# UBTB_MIX.net
KiCad netlist of a schematic drawn in EAGLE
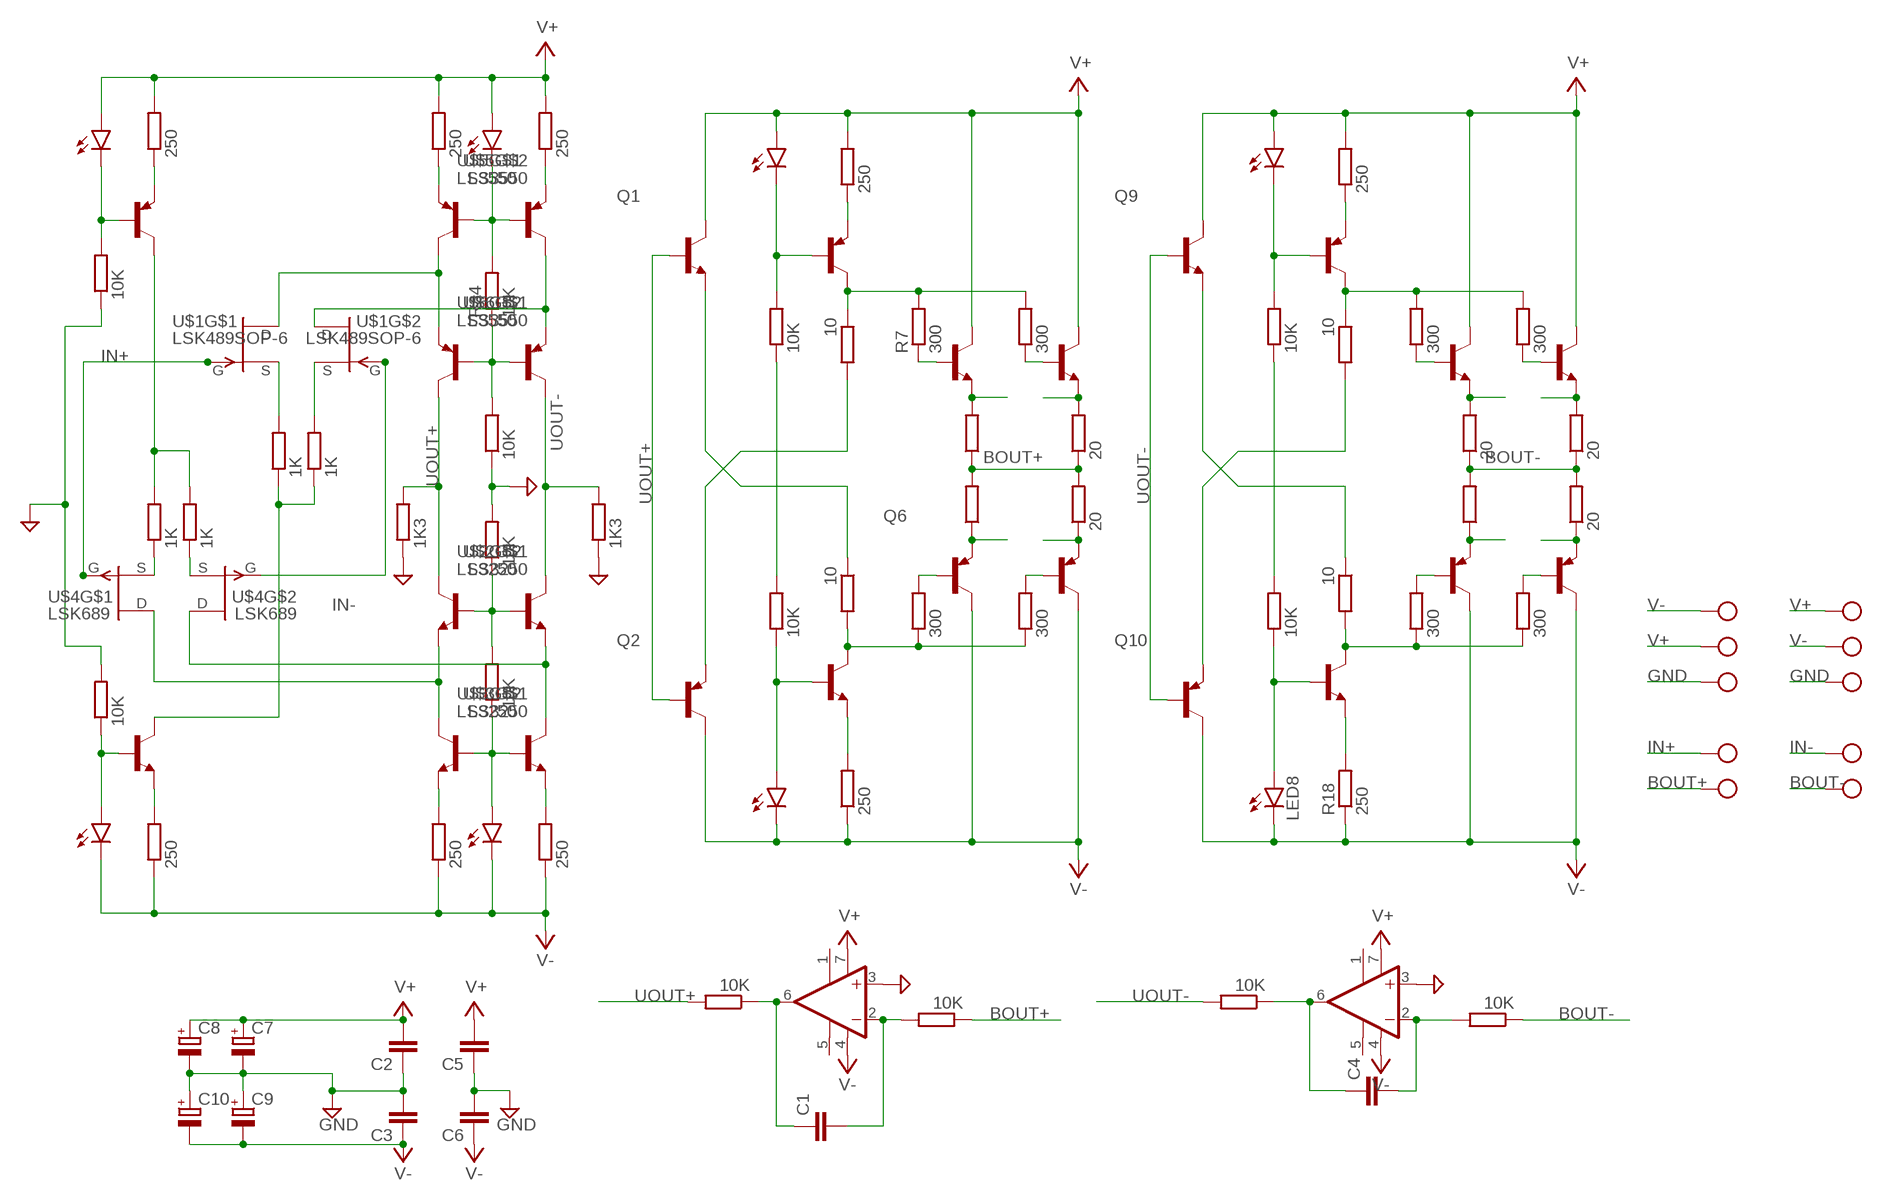
[diagram p0: schematic, sheet 1]

(export (version "E")
  (design (tool "Eeschema 10.0.6"))
  (components
    (comp (ref "C1")
      (value "C-EUC1206")
      (footprint "eagle-import:C1206")
      (libsource (lib "eagle-import") (part "C-EUC1206"))
    )
    (comp (ref "C2")
      (value "C-EUC0805")
      (footprint "eagle-import:C0805")
      (libsource (lib "eagle-import") (part "C-EUC0805"))
    )
    (comp (ref "C3")
      (value "C-EUC0805")
      (footprint "eagle-import:C0805")
      (libsource (lib "eagle-import") (part "C-EUC0805"))
    )
    (comp (ref "C4")
      (value "C-EUC1206")
      (footprint "eagle-import:C1206")
      (libsource (lib "eagle-import") (part "C-EUC1206"))
    )
    (comp (ref "C5")
      (value "C-EUC0805")
      (footprint "eagle-import:C0805")
      (libsource (lib "eagle-import") (part "C-EUC0805"))
    )
    (comp (ref "C6")
      (value "C-EUC0805")
      (footprint "eagle-import:C0805")
      (libsource (lib "eagle-import") (part "C-EUC0805"))
    )
    (comp (ref "C7")
      (value "CPOL-EUF")
      (footprint "eagle-import:PANASONIC_F")
      (libsource (lib "eagle-import") (part "CPOL-EUF"))
    )
    (comp (ref "C8")
      (value "CPOL-EUF")
      (footprint "eagle-import:PANASONIC_F")
      (libsource (lib "eagle-import") (part "CPOL-EUF"))
    )
    (comp (ref "C9")
      (value "CPOL-EUF")
      (footprint "eagle-import:PANASONIC_F")
      (libsource (lib "eagle-import") (part "CPOL-EUF"))
    )
    (comp (ref "C10")
      (value "CPOL-EUF")
      (footprint "eagle-import:PANASONIC_F")
      (libsource (lib "eagle-import") (part "CPOL-EUF"))
    )
    (comp (ref "IC1")
      (value "OPA627U")
      (footprint "eagle-import:SO08")
      (fields (field (name "MF") "TEXAS INSTRUMENTS") (field (name "MPN") "OPA627AU"))
      (libsource (lib "eagle-import") (part "OPA627U"))
    )
    (comp (ref "IC2")
      (value "OPA627U")
      (footprint "eagle-import:SO08")
      (fields (field (name "MF") "TEXAS INSTRUMENTS") (field (name "MPN") "OPA627AU"))
      (libsource (lib "eagle-import") (part "OPA627U"))
    )
    (comp (ref "LED1")
      (value "LEDVWV1206")
      (footprint "eagle-import:LED_SML1206")
      (libsource (lib "eagle-import") (part "LEDVWV1206"))
    )
    (comp (ref "LED2")
      (value "LEDVWV1206")
      (footprint "eagle-import:LED_SML1206")
      (libsource (lib "eagle-import") (part "LEDVWV1206"))
    )
    (comp (ref "LED3")
      (value "LEDVWV1206")
      (footprint "eagle-import:LED_SML1206")
      (libsource (lib "eagle-import") (part "LEDVWV1206"))
    )
    (comp (ref "LED4")
      (value "LEDVWV1206")
      (footprint "eagle-import:LED_SML1206")
      (fields (field (name "SPICEPREFIX") "D"))
      (libsource (lib "eagle-import") (part "LEDVWV1206"))
    )
    (comp (ref "LED5")
      (value "LEDVWV1206")
      (footprint "eagle-import:LED_SML1206")
      (libsource (lib "eagle-import") (part "LEDVWV1206"))
    )
    (comp (ref "LED6")
      (value "LEDVWV1206")
      (footprint "eagle-import:LED_SML1206")
      (libsource (lib "eagle-import") (part "LEDVWV1206"))
    )
    (comp (ref "LED7")
      (value "LEDVWV1206")
      (footprint "eagle-import:LED_SML1206")
      (libsource (lib "eagle-import") (part "LEDVWV1206"))
    )
    (comp (ref "LED8")
      (value "LEDVWV1206")
      (footprint "eagle-import:LED_SML1206")
      (libsource (lib "eagle-import") (part "LEDVWV1206"))
    )
    (comp (ref "Q1")
      (value "TRANSISTOR_BC846-NPN-SOT23-BEC")
      (footprint "eagle-import:TRANSISTOR_SOT23-BEC")
      (libsource (lib "eagle-import") (part "TRANSISTOR_-NPN-SOT23-BECBC846"))
    )
    (comp (ref "Q2")
      (value "TRANSISTOR_BC856B-PNP-SOT23-BEC")
      (footprint "eagle-import:TRANSISTOR_SOT23-BEC")
      (libsource (lib "eagle-import") (part "TRANSISTOR_-PNP-SOT23-BECBC856B"))
    )
    (comp (ref "Q3")
      (value "TRANSISTOR_BC846-NPN-SOT23-BEC")
      (footprint "eagle-import:TRANSISTOR_SOT23-BEC")
      (libsource (lib "eagle-import") (part "TRANSISTOR_-NPN-SOT23-BECBC846"))
    )
    (comp (ref "Q4")
      (value "TRANSISTOR_BC856B-PNP-SOT23-BEC")
      (footprint "eagle-import:TRANSISTOR_SOT23-BEC")
      (libsource (lib "eagle-import") (part "TRANSISTOR_-PNP-SOT23-BECBC856B"))
    )
    (comp (ref "Q5")
      (value "TRANSISTOR_BC846-NPN-SOT23-BEC")
      (footprint "eagle-import:TRANSISTOR_SOT23-BEC")
      (libsource (lib "eagle-import") (part "TRANSISTOR_-NPN-SOT23-BECBC846"))
    )
    (comp (ref "Q6")
      (value "TRANSISTOR_BC856B-PNP-SOT23-BEC")
      (footprint "eagle-import:TRANSISTOR_SOT23-BEC")
      (libsource (lib "eagle-import") (part "TRANSISTOR_-PNP-SOT23-BECBC856B"))
    )
    (comp (ref "Q7")
      (value "TRANSISTOR_BC856B-PNP-SOT23-BEC")
      (footprint "eagle-import:TRANSISTOR_SOT23-BEC")
      (libsource (lib "eagle-import") (part "TRANSISTOR_-PNP-SOT23-BECBC856B"))
    )
    (comp (ref "Q8")
      (value "TRANSISTOR_BC846-NPN-SOT23-BEC")
      (footprint "eagle-import:TRANSISTOR_SOT23-BEC")
      (libsource (lib "eagle-import") (part "TRANSISTOR_-NPN-SOT23-BECBC846"))
    )
    (comp (ref "Q9")
      (value "TRANSISTOR_BC846-NPN-SOT23-BEC")
      (footprint "eagle-import:TRANSISTOR_SOT23-BEC")
      (libsource (lib "eagle-import") (part "TRANSISTOR_-NPN-SOT23-BECBC846"))
    )
    (comp (ref "Q10")
      (value "TRANSISTOR_BC856B-PNP-SOT23-BEC")
      (footprint "eagle-import:TRANSISTOR_SOT23-BEC")
      (libsource (lib "eagle-import") (part "TRANSISTOR_-PNP-SOT23-BECBC856B"))
    )
    (comp (ref "Q11")
      (value "TRANSISTOR_BC846-NPN-SOT23-BEC")
      (footprint "eagle-import:TRANSISTOR_SOT23-BEC")
      (libsource (lib "eagle-import") (part "TRANSISTOR_-NPN-SOT23-BECBC846"))
    )
    (comp (ref "Q12")
      (value "TRANSISTOR_BC856B-PNP-SOT23-BEC")
      (footprint "eagle-import:TRANSISTOR_SOT23-BEC")
      (libsource (lib "eagle-import") (part "TRANSISTOR_-PNP-SOT23-BECBC856B"))
    )
    (comp (ref "Q13")
      (value "TRANSISTOR_BC846-NPN-SOT23-BEC")
      (footprint "eagle-import:TRANSISTOR_SOT23-BEC")
      (libsource (lib "eagle-import") (part "TRANSISTOR_-NPN-SOT23-BECBC846"))
    )
    (comp (ref "Q14")
      (value "TRANSISTOR_BC846-NPN-SOT23-BEC")
      (footprint "eagle-import:TRANSISTOR_SOT23-BEC")
      (libsource (lib "eagle-import") (part "TRANSISTOR_-NPN-SOT23-BECBC846"))
    )
    (comp (ref "Q15")
      (value "TRANSISTOR_BC856B-PNP-SOT23-BEC")
      (footprint "eagle-import:TRANSISTOR_SOT23-BEC")
      (libsource (lib "eagle-import") (part "TRANSISTOR_-PNP-SOT23-BECBC856B"))
    )
    (comp (ref "Q16")
      (value "TRANSISTOR_BC856B-PNP-SOT23-BEC")
      (footprint "eagle-import:TRANSISTOR_SOT23-BEC")
      (libsource (lib "eagle-import") (part "TRANSISTOR_-PNP-SOT23-BECBC856B"))
    )
    (comp (ref "Q17")
      (value "TRANSISTOR_BC846-NPN-SOT23-BEC")
      (footprint "eagle-import:TRANSISTOR_SOT23-BEC")
      (libsource (lib "eagle-import") (part "TRANSISTOR_-NPN-SOT23-BECBC846"))
    )
    (comp (ref "Q18")
      (value "TRANSISTOR_BC856B-PNP-SOT23-BEC")
      (footprint "eagle-import:TRANSISTOR_SOT23-BEC")
      (libsource (lib "eagle-import") (part "TRANSISTOR_-PNP-SOT23-BECBC856B"))
    )
    (comp (ref "R1")
      (value "250")
      (footprint "eagle-import:MINI_MELF-0204W")
      (libsource (lib "eagle-import") (part "R-EU_MELF0204W"))
    )
    (comp (ref "R2")
      (value "250")
      (footprint "eagle-import:MINI_MELF-0204W")
      (libsource (lib "eagle-import") (part "R-EU_MELF0204W"))
    )
    (comp (ref "R3")
      (value "10K")
      (footprint "eagle-import:MINI_MELF-0204W")
      (libsource (lib "eagle-import") (part "R-EU_MELF0204W"))
    )
    (comp (ref "R4")
      (value "10K")
      (footprint "eagle-import:MINI_MELF-0204W")
      (libsource (lib "eagle-import") (part "R-EU_MELF0204W"))
    )
    (comp (ref "R5")
      (value "10")
      (footprint "eagle-import:MINI_MELF-0204W")
      (libsource (lib "eagle-import") (part "R-EU_MELF0204W"))
    )
    (comp (ref "R6")
      (value "10")
      (footprint "eagle-import:MINI_MELF-0204W")
      (libsource (lib "eagle-import") (part "R-EU_MELF0204W"))
    )
    (comp (ref "R7")
      (value "300")
      (footprint "eagle-import:MINI_MELF-0204W")
      (libsource (lib "eagle-import") (part "R-EU_MELF0204W"))
    )
    (comp (ref "R8")
      (value "300")
      (footprint "eagle-import:MINI_MELF-0204W")
      (libsource (lib "eagle-import") (part "R-EU_MELF0204W"))
    )
    (comp (ref "R9")
      (value "300")
      (footprint "eagle-import:MINI_MELF-0204W")
      (libsource (lib "eagle-import") (part "R-EU_MELF0204W"))
    )
    (comp (ref "R10")
      (value "300")
      (footprint "eagle-import:MINI_MELF-0204W")
      (libsource (lib "eagle-import") (part "R-EU_MELF0204W"))
    )
    (comp (ref "R11")
      (value "R-EU_MELF0204W")
      (footprint "eagle-import:MINI_MELF-0204W")
      (libsource (lib "eagle-import") (part "R-EU_MELF0204W"))
    )
    (comp (ref "R12")
      (value "R-EU_MELF0204W")
      (footprint "eagle-import:MINI_MELF-0204W")
      (libsource (lib "eagle-import") (part "R-EU_MELF0204W"))
    )
    (comp (ref "R13")
      (value "20")
      (footprint "eagle-import:MINI_MELF-0204W")
      (libsource (lib "eagle-import") (part "R-EU_MELF0204W"))
    )
    (comp (ref "R14")
      (value "20")
      (footprint "eagle-import:MINI_MELF-0204W")
      (libsource (lib "eagle-import") (part "R-EU_MELF0204W"))
    )
    (comp (ref "R15")
      (value "250")
      (footprint "eagle-import:MINI_MELF-0204W")
      (libsource (lib "eagle-import") (part "R-EU_MELF0204W"))
    )
    (comp (ref "R16")
      (value "10K")
      (footprint "eagle-import:MINI_MELF-0204W")
      (libsource (lib "eagle-import") (part "R-EU_MELF0204W"))
    )
    (comp (ref "R17")
      (value "10K")
      (footprint "eagle-import:MINI_MELF-0204W")
      (libsource (lib "eagle-import") (part "R-EU_MELF0204W"))
    )
    (comp (ref "R18")
      (value "250")
      (footprint "eagle-import:MINI_MELF-0204W")
      (libsource (lib "eagle-import") (part "R-EU_MELF0204W"))
    )
    (comp (ref "R19")
      (value "10K")
      (footprint "eagle-import:MINI_MELF-0204W")
      (libsource (lib "eagle-import") (part "R-EU_MELF0204W"))
    )
    (comp (ref "R20")
      (value "10K")
      (footprint "eagle-import:MINI_MELF-0204W")
      (libsource (lib "eagle-import") (part "R-EU_MELF0204W"))
    )
    (comp (ref "R21")
      (value "10")
      (footprint "eagle-import:MINI_MELF-0204W")
      (libsource (lib "eagle-import") (part "R-EU_MELF0204W"))
    )
    (comp (ref "R22")
      (value "250")
      (footprint "eagle-import:MINI_MELF-0204W")
      (libsource (lib "eagle-import") (part "R-EU_MELF0204W"))
    )
    (comp (ref "R23")
      (value "250")
      (footprint "eagle-import:MINI_MELF-0204W")
      (libsource (lib "eagle-import") (part "R-EU_MELF0204W"))
    )
    (comp (ref "R24")
      (value "10")
      (footprint "eagle-import:MINI_MELF-0204W")
      (libsource (lib "eagle-import") (part "R-EU_MELF0204W"))
    )
    (comp (ref "R25")
      (value "300")
      (footprint "eagle-import:MINI_MELF-0204W")
      (libsource (lib "eagle-import") (part "R-EU_MELF0204W"))
    )
    (comp (ref "R26")
      (value "300")
      (footprint "eagle-import:MINI_MELF-0204W")
      (libsource (lib "eagle-import") (part "R-EU_MELF0204W"))
    )
    (comp (ref "R27")
      (value "300")
      (footprint "eagle-import:MINI_MELF-0204W")
      (libsource (lib "eagle-import") (part "R-EU_MELF0204W"))
    )
    (comp (ref "R28")
      (value "300")
      (footprint "eagle-import:MINI_MELF-0204W")
      (libsource (lib "eagle-import") (part "R-EU_MELF0204W"))
    )
    (comp (ref "R29")
      (value "10K")
      (footprint "eagle-import:MINI_MELF-0204W")
      (libsource (lib "eagle-import") (part "R-EU_MELF0204W"))
    )
    (comp (ref "R30")
      (value "20")
      (footprint "eagle-import:MINI_MELF-0204W")
      (libsource (lib "eagle-import") (part "R-EU_MELF0204W"))
    )
    (comp (ref "R31")
      (value "R-EU_MELF0204W")
      (footprint "eagle-import:MINI_MELF-0204W")
      (libsource (lib "eagle-import") (part "R-EU_MELF0204W"))
    )
    (comp (ref "R32")
      (value "10K")
      (footprint "eagle-import:MINI_MELF-0204W")
      (libsource (lib "eagle-import") (part "R-EU_MELF0204W"))
    )
    (comp (ref "R33")
      (value "10K")
      (footprint "eagle-import:MINI_MELF-0204W")
      (libsource (lib "eagle-import") (part "R-EU_MELF0204W"))
    )
    (comp (ref "R34")
      (value "10K")
      (footprint "eagle-import:MINI_MELF-0204W")
      (libsource (lib "eagle-import") (part "R-EU_MELF0204W"))
    )
    (comp (ref "R35")
      (value "250")
      (footprint "eagle-import:MINI_MELF-0204W")
      (libsource (lib "eagle-import") (part "R-EU_MELF0204W"))
    )
    (comp (ref "R36")
      (value "250")
      (footprint "eagle-import:MINI_MELF-0204W")
      (libsource (lib "eagle-import") (part "R-EU_MELF0204W"))
    )
    (comp (ref "R37")
      (value "1K3")
      (footprint "eagle-import:MINI_MELF-0204W")
      (libsource (lib "eagle-import") (part "R-EU_MELF0204W"))
    )
    (comp (ref "R38")
      (value "1K3")
      (footprint "eagle-import:MINI_MELF-0204W")
      (libsource (lib "eagle-import") (part "R-EU_MELF0204W"))
    )
    (comp (ref "R39")
      (value "1K")
      (footprint "eagle-import:MINI_MELF-0204W")
      (libsource (lib "eagle-import") (part "R-EU_MELF0204W"))
    )
    (comp (ref "R40")
      (value "1K")
      (footprint "eagle-import:MINI_MELF-0204W")
      (libsource (lib "eagle-import") (part "R-EU_MELF0204W"))
    )
    (comp (ref "R41")
      (value "1K")
      (footprint "eagle-import:MINI_MELF-0204W")
      (libsource (lib "eagle-import") (part "R-EU_MELF0204W"))
    )
    (comp (ref "R42")
      (value "1K")
      (footprint "eagle-import:MINI_MELF-0204W")
      (libsource (lib "eagle-import") (part "R-EU_MELF0204W"))
    )
    (comp (ref "R43")
      (value "250")
      (footprint "eagle-import:MINI_MELF-0204W")
      (libsource (lib "eagle-import") (part "R-EU_MELF0204W"))
    )
    (comp (ref "R44")
      (value "250")
      (footprint "eagle-import:MINI_MELF-0204W")
      (fields (field (name "SPICEPREFIX") "R"))
      (libsource (lib "eagle-import") (part "R-EU_MELF0204W"))
    )
    (comp (ref "R45")
      (value "10K")
      (footprint "eagle-import:MINI_MELF-0204W")
      (libsource (lib "eagle-import") (part "R-EU_MELF0204W"))
    )
    (comp (ref "R46")
      (value "10K")
      (footprint "eagle-import:MINI_MELF-0204W")
      (libsource (lib "eagle-import") (part "R-EU_MELF0204W"))
    )
    (comp (ref "R47")
      (value "20")
      (footprint "eagle-import:MINI_MELF-0204W")
      (libsource (lib "eagle-import") (part "R-EU_MELF0204W"))
    )
    (comp (ref "R48")
      (value "10K")
      (footprint "eagle-import:MINI_MELF-0204W")
      (libsource (lib "eagle-import") (part "R-EU_MELF0204W"))
    )
    (comp (ref "R49")
      (value "20")
      (footprint "eagle-import:MINI_MELF-0204W")
      (libsource (lib "eagle-import") (part "R-EU_MELF0204W"))
    )
    (comp (ref "R51")
      (value "10K")
      (footprint "eagle-import:MINI_MELF-0204W")
      (libsource (lib "eagle-import") (part "R-EU_MELF0204W"))
    )
    (comp (ref "U$1")
      (value "LSK489SOP-6")
      (footprint "eagle-import:SOT-23-6")
      (libsource (lib "eagle-import") (part "LSK489SOP-6"))
    )
    (comp (ref "U$2")
      (value "LS3250")
      (footprint "eagle-import:SOT-23-6")
      (libsource (lib "eagle-import") (part "LS3250"))
    )
    (comp (ref "U$3")
      (value "LS3250")
      (footprint "eagle-import:SOT-23-6")
      (libsource (lib "eagle-import") (part "LS3250"))
    )
    (comp (ref "U$4")
      (value "LSK689")
      (footprint "eagle-import:SOT-23-6")
      (libsource (lib "eagle-import") (part "LSK689"))
    )
    (comp (ref "U$5")
      (value "LS3550")
      (footprint "eagle-import:SOT-23-6")
      (libsource (lib "eagle-import") (part "LS3550"))
    )
    (comp (ref "U$6")
      (value "LS3550")
      (footprint "eagle-import:SOT-23-6")
      (libsource (lib "eagle-import") (part "LS3550"))
    )
    (comp (ref "X1")
      (value "CON-PHOENIX-508_MKDSN1,5/3-5,08")
      (footprint "eagle-import:CON-PHOENIX-508_MKDSN1,5_3-5,08")
      (libsource (lib "eagle-import") (part "CON-PHOENIX-508_MKDSN1,5/3-5,08"))
    )
    (comp (ref "X2")
      (value "CON-PHOENIX-508_MKDSN1,5/3-5,08")
      (footprint "eagle-import:CON-PHOENIX-508_MKDSN1,5_3-5,08")
      (libsource (lib "eagle-import") (part "CON-PHOENIX-508_MKDSN1,5/3-5,08"))
    )
    (comp (ref "X3")
      (value "CON-PHOENIX-508_MKDSN1,5/2-5,08")
      (footprint "eagle-import:CON-PHOENIX-508_MKDSN1,5_2-5,08")
      (libsource (lib "eagle-import") (part "CON-PHOENIX-508_MKDSN1,5/2-5,08"))
    )
    (comp (ref "X4")
      (value "CON-PHOENIX-508_MKDSN1,5/2-5,08")
      (footprint "eagle-import:CON-PHOENIX-508_MKDSN1,5_2-5,08")
      (libsource (lib "eagle-import") (part "CON-PHOENIX-508_MKDSN1,5/2-5,08"))
    )
  )
  (nets
    (net (code "1") (name "/BOUT+") (class "Default")
      (node (ref "R11") (pin "1") (pinfunction "1_1") (pintype "passive"))
      (node (ref "R12") (pin "2") (pinfunction "2_2") (pintype "passive"))
      (node (ref "R13") (pin "1") (pinfunction "1_1") (pintype "passive"))
      (node (ref "R14") (pin "2") (pinfunction "2_2") (pintype "passive"))
      (node (ref "R17") (pin "1") (pinfunction "1_1") (pintype "passive"))
      (node (ref "X3") (pin "2") (pinfunction "KL_2") (pintype "passive"))
    )
    (net (code "2") (name "/BOUT-") (class "Default")
      (node (ref "R30") (pin "1") (pinfunction "1_1") (pintype "passive"))
      (node (ref "R31") (pin "2") (pinfunction "2_2") (pintype "passive"))
      (node (ref "R47") (pin "1") (pinfunction "1_1") (pintype "passive"))
      (node (ref "R48") (pin "1") (pinfunction "1_1") (pintype "passive"))
      (node (ref "R49") (pin "2") (pinfunction "2_2") (pintype "passive"))
      (node (ref "X4") (pin "2") (pinfunction "KL_2") (pintype "passive"))
    )
    (net (code "3") (name "/IN+") (class "Default")
      (node (ref "U$1") (pin "1") (pinfunction "G_1") (pintype "passive"))
      (node (ref "U$4") (pin "1") (pinfunction "G_1") (pintype "passive"))
      (node (ref "X3") (pin "1") (pinfunction "KL_1") (pintype "passive"))
    )
    (net (code "4") (name "/IN-") (class "Default")
      (node (ref "U$1") (pin "4") (pinfunction "G_4") (pintype "passive"))
      (node (ref "U$4") (pin "4") (pinfunction "G_4") (pintype "passive"))
      (node (ref "X4") (pin "1") (pinfunction "KL_1") (pintype "passive"))
    )
    (net (code "5") (name "/UOUT+") (class "Default")
      (node (ref "Q1") (pin "B") (pinfunction "B_B") (pintype "passive"))
      (node (ref "Q2") (pin "B") (pinfunction "B_B") (pintype "passive"))
      (node (ref "R16") (pin "2") (pinfunction "2_2") (pintype "passive"))
      (node (ref "R37") (pin "2") (pinfunction "2_2") (pintype "passive"))
      (node (ref "U$2") (pin "6") (pinfunction "C_6") (pintype "passive"))
      (node (ref "U$6") (pin "6") (pinfunction "C_6") (pintype "passive"))
    )
    (net (code "6") (name "/UOUT-") (class "Default")
      (node (ref "Q10") (pin "B") (pinfunction "B_B") (pintype "passive"))
      (node (ref "Q9") (pin "B") (pinfunction "B_B") (pintype "passive"))
      (node (ref "R38") (pin "2") (pinfunction "2_2") (pintype "passive"))
      (node (ref "R51") (pin "2") (pinfunction "2_2") (pintype "passive"))
      (node (ref "U$2") (pin "4") (pinfunction "C_4") (pintype "passive"))
      (node (ref "U$6") (pin "4") (pinfunction "C_4") (pintype "passive"))
    )
    (net (code "7") (name "GND") (class "Default")
      (node (ref "C10") (pin "+") (pinfunction "+_+") (pintype "passive"))
      (node (ref "C2") (pin "1") (pinfunction "1_1") (pintype "passive"))
      (node (ref "C3") (pin "2") (pinfunction "2_2") (pintype "passive"))
      (node (ref "C5") (pin "1") (pinfunction "1_1") (pintype "passive"))
      (node (ref "C6") (pin "2") (pinfunction "2_2") (pintype "passive"))
      (node (ref "C7") (pin "-") (pinfunction "-_-") (pintype "passive"))
      (node (ref "C8") (pin "-") (pinfunction "-_-") (pintype "passive"))
      (node (ref "C9") (pin "+") (pinfunction "+_+") (pintype "passive"))
      (node (ref "IC1") (pin "3") (pinfunction "+IN_3") (pintype "input"))
      (node (ref "IC2") (pin "3") (pinfunction "+IN_3") (pintype "input"))
      (node (ref "R32") (pin "2") (pinfunction "2_2") (pintype "passive"))
      (node (ref "R33") (pin "1") (pinfunction "1_1") (pintype "passive"))
      (node (ref "R37") (pin "1") (pinfunction "1_1") (pintype "passive"))
      (node (ref "R38") (pin "1") (pinfunction "1_1") (pintype "passive"))
      (node (ref "R45") (pin "1") (pinfunction "1_1") (pintype "passive"))
      (node (ref "R46") (pin "2") (pinfunction "2_2") (pintype "passive"))
      (node (ref "X1") (pin "3") (pinfunction "KL_3") (pintype "passive"))
      (node (ref "X2") (pin "3") (pinfunction "KL_3") (pintype "passive"))
    )
    (net (code "8") (name "Net-(IC1--IN)") (class "Default")
      (node (ref "C1") (pin "2") (pinfunction "2_2") (pintype "passive"))
      (node (ref "IC1") (pin "2") (pinfunction "-IN_2") (pintype "input"))
      (node (ref "R17") (pin "2") (pinfunction "2_2") (pintype "passive"))
    )
    (net (code "9") (name "Net-(IC1-OUT)") (class "Default")
      (node (ref "C1") (pin "1") (pinfunction "1_1") (pintype "passive"))
      (node (ref "IC1") (pin "6") (pinfunction "OUT_6") (pintype "output"))
      (node (ref "R16") (pin "1") (pinfunction "1_1") (pintype "passive"))
    )
    (net (code "10") (name "Net-(IC2--IN)") (class "Default")
      (node (ref "C4") (pin "2") (pinfunction "2_2") (pintype "passive"))
      (node (ref "IC2") (pin "2") (pinfunction "-IN_2") (pintype "input"))
      (node (ref "R48") (pin "2") (pinfunction "2_2") (pintype "passive"))
    )
    (net (code "11") (name "Net-(IC2-OUT)") (class "Default")
      (node (ref "C4") (pin "1") (pinfunction "1_1") (pintype "passive"))
      (node (ref "IC2") (pin "6") (pinfunction "OUT_6") (pintype "output"))
      (node (ref "R51") (pin "1") (pinfunction "1_1") (pintype "passive"))
    )
    (net (code "12") (name "Net-(LED3-PadC)") (class "Default")
      (node (ref "LED3") (pin "C") (pinfunction "C_C") (pintype "passive"))
      (node (ref "Q18") (pin "B") (pinfunction "B_B") (pintype "passive"))
      (node (ref "R45") (pin "2") (pinfunction "2_2") (pintype "passive"))
    )
    (net (code "13") (name "Net-(LED4-PadA)") (class "Default")
      (node (ref "LED4") (pin "A") (pinfunction "A_A") (pintype "passive"))
      (node (ref "Q17") (pin "B") (pinfunction "B_B") (pintype "passive"))
      (node (ref "R46") (pin "1") (pinfunction "1_1") (pintype "passive"))
    )
    (net (code "14") (name "Net-(LED5-PadC)") (class "Default")
      (node (ref "LED5") (pin "C") (pinfunction "C_C") (pintype "passive"))
      (node (ref "Q4") (pin "B") (pinfunction "B_B") (pintype "passive"))
      (node (ref "R3") (pin "2") (pinfunction "2_2") (pintype "passive"))
    )
    (net (code "15") (name "Net-(LED6-PadA)") (class "Default")
      (node (ref "LED6") (pin "A") (pinfunction "A_A") (pintype "passive"))
      (node (ref "Q3") (pin "B") (pinfunction "B_B") (pintype "passive"))
      (node (ref "R4") (pin "1") (pinfunction "1_1") (pintype "passive"))
    )
    (net (code "16") (name "Net-(LED7-PadC)") (class "Default")
      (node (ref "LED7") (pin "C") (pinfunction "C_C") (pintype "passive"))
      (node (ref "Q12") (pin "B") (pinfunction "B_B") (pintype "passive"))
      (node (ref "R19") (pin "2") (pinfunction "2_2") (pintype "passive"))
    )
    (net (code "17") (name "Net-(LED8-PadA)") (class "Default")
      (node (ref "LED8") (pin "A") (pinfunction "A_A") (pintype "passive"))
      (node (ref "Q11") (pin "B") (pinfunction "B_B") (pintype "passive"))
      (node (ref "R20") (pin "1") (pinfunction "1_1") (pintype "passive"))
    )
    (net (code "18") (name "Net-(Q1-PadE)") (class "Default")
      (node (ref "Q1") (pin "E") (pinfunction "E_E") (pintype "passive"))
      (node (ref "R6") (pin "1") (pinfunction "1_1") (pintype "passive"))
    )
    (net (code "19") (name "Net-(Q2-PadE)") (class "Default")
      (node (ref "Q2") (pin "E") (pinfunction "E_E") (pintype "passive"))
      (node (ref "R5") (pin "2") (pinfunction "2_2") (pintype "passive"))
    )
    (net (code "20") (name "Net-(Q3-PadC)") (class "Default")
      (node (ref "Q3") (pin "C") (pinfunction "C_C") (pintype "passive"))
      (node (ref "R6") (pin "2") (pinfunction "2_2") (pintype "passive"))
      (node (ref "R8") (pin "1") (pinfunction "1_1") (pintype "passive"))
      (node (ref "R9") (pin "1") (pinfunction "1_1") (pintype "passive"))
    )
    (net (code "21") (name "Net-(Q3-PadE)") (class "Default")
      (node (ref "Q3") (pin "E") (pinfunction "E_E") (pintype "passive"))
      (node (ref "R2") (pin "2") (pinfunction "2_2") (pintype "passive"))
    )
    (net (code "22") (name "Net-(Q4-PadC)") (class "Default")
      (node (ref "Q4") (pin "C") (pinfunction "C_C") (pintype "passive"))
      (node (ref "R10") (pin "2") (pinfunction "2_2") (pintype "passive"))
      (node (ref "R5") (pin "1") (pinfunction "1_1") (pintype "passive"))
      (node (ref "R7") (pin "2") (pinfunction "2_2") (pintype "passive"))
    )
    (net (code "23") (name "Net-(Q4-PadE)") (class "Default")
      (node (ref "Q4") (pin "E") (pinfunction "E_E") (pintype "passive"))
      (node (ref "R1") (pin "1") (pinfunction "1_1") (pintype "passive"))
    )
    (net (code "24") (name "Net-(Q5-PadB)") (class "Default")
      (node (ref "Q5") (pin "B") (pinfunction "B_B") (pintype "passive"))
      (node (ref "R7") (pin "1") (pinfunction "1_1") (pintype "passive"))
    )
    (net (code "25") (name "Net-(Q5-PadE)") (class "Default")
      (node (ref "Q5") (pin "E") (pinfunction "E_E") (pintype "passive"))
      (node (ref "R11") (pin "2") (pinfunction "2_2") (pintype "passive"))
    )
    (net (code "26") (name "Net-(Q6-PadB)") (class "Default")
      (node (ref "Q6") (pin "B") (pinfunction "B_B") (pintype "passive"))
      (node (ref "R8") (pin "2") (pinfunction "2_2") (pintype "passive"))
    )
    (net (code "27") (name "Net-(Q6-PadE)") (class "Default")
      (node (ref "Q6") (pin "E") (pinfunction "E_E") (pintype "passive"))
      (node (ref "R12") (pin "1") (pinfunction "1_1") (pintype "passive"))
    )
    (net (code "28") (name "Net-(Q7-PadB)") (class "Default")
      (node (ref "Q7") (pin "B") (pinfunction "B_B") (pintype "passive"))
      (node (ref "R9") (pin "2") (pinfunction "2_2") (pintype "passive"))
    )
    (net (code "29") (name "Net-(Q7-PadE)") (class "Default")
      (node (ref "Q7") (pin "E") (pinfunction "E_E") (pintype "passive"))
      (node (ref "R14") (pin "1") (pinfunction "1_1") (pintype "passive"))
    )
    (net (code "30") (name "Net-(Q8-PadB)") (class "Default")
      (node (ref "Q8") (pin "B") (pinfunction "B_B") (pintype "passive"))
      (node (ref "R10") (pin "1") (pinfunction "1_1") (pintype "passive"))
    )
    (net (code "31") (name "Net-(Q8-PadE)") (class "Default")
      (node (ref "Q8") (pin "E") (pinfunction "E_E") (pintype "passive"))
      (node (ref "R13") (pin "2") (pinfunction "2_2") (pintype "passive"))
    )
    (net (code "32") (name "Net-(Q9-PadE)") (class "Default")
      (node (ref "Q9") (pin "E") (pinfunction "E_E") (pintype "passive"))
      (node (ref "R24") (pin "1") (pinfunction "1_1") (pintype "passive"))
    )
    (net (code "33") (name "Net-(Q10-PadE)") (class "Default")
      (node (ref "Q10") (pin "E") (pinfunction "E_E") (pintype "passive"))
      (node (ref "R21") (pin "2") (pinfunction "2_2") (pintype "passive"))
    )
    (net (code "34") (name "Net-(Q11-PadC)") (class "Default")
      (node (ref "Q11") (pin "C") (pinfunction "C_C") (pintype "passive"))
      (node (ref "R24") (pin "2") (pinfunction "2_2") (pintype "passive"))
      (node (ref "R26") (pin "1") (pinfunction "1_1") (pintype "passive"))
      (node (ref "R27") (pin "1") (pinfunction "1_1") (pintype "passive"))
    )
    (net (code "35") (name "Net-(Q11-PadE)") (class "Default")
      (node (ref "Q11") (pin "E") (pinfunction "E_E") (pintype "passive"))
      (node (ref "R18") (pin "2") (pinfunction "2_2") (pintype "passive"))
    )
    (net (code "36") (name "Net-(Q12-PadC)") (class "Default")
      (node (ref "Q12") (pin "C") (pinfunction "C_C") (pintype "passive"))
      (node (ref "R21") (pin "1") (pinfunction "1_1") (pintype "passive"))
      (node (ref "R25") (pin "2") (pinfunction "2_2") (pintype "passive"))
      (node (ref "R28") (pin "2") (pinfunction "2_2") (pintype "passive"))
    )
    (net (code "37") (name "Net-(Q12-PadE)") (class "Default")
      (node (ref "Q12") (pin "E") (pinfunction "E_E") (pintype "passive"))
      (node (ref "R15") (pin "1") (pinfunction "1_1") (pintype "passive"))
    )
    (net (code "38") (name "Net-(Q13-PadB)") (class "Default")
      (node (ref "Q13") (pin "B") (pinfunction "B_B") (pintype "passive"))
      (node (ref "R25") (pin "1") (pinfunction "1_1") (pintype "passive"))
    )
    (net (code "39") (name "Net-(Q13-PadE)") (class "Default")
      (node (ref "Q13") (pin "E") (pinfunction "E_E") (pintype "passive"))
      (node (ref "R30") (pin "2") (pinfunction "2_2") (pintype "passive"))
    )
    (net (code "40") (name "Net-(Q14-PadB)") (class "Default")
      (node (ref "Q14") (pin "B") (pinfunction "B_B") (pintype "passive"))
      (node (ref "R28") (pin "1") (pinfunction "1_1") (pintype "passive"))
    )
    (net (code "41") (name "Net-(Q14-PadE)") (class "Default")
      (node (ref "Q14") (pin "E") (pinfunction "E_E") (pintype "passive"))
      (node (ref "R47") (pin "2") (pinfunction "2_2") (pintype "passive"))
    )
    (net (code "42") (name "Net-(Q15-PadB)") (class "Default")
      (node (ref "Q15") (pin "B") (pinfunction "B_B") (pintype "passive"))
      (node (ref "R26") (pin "2") (pinfunction "2_2") (pintype "passive"))
    )
    (net (code "43") (name "Net-(Q15-PadE)") (class "Default")
      (node (ref "Q15") (pin "E") (pinfunction "E_E") (pintype "passive"))
      (node (ref "R31") (pin "1") (pinfunction "1_1") (pintype "passive"))
    )
    (net (code "44") (name "Net-(Q16-PadB)") (class "Default")
      (node (ref "Q16") (pin "B") (pinfunction "B_B") (pintype "passive"))
      (node (ref "R27") (pin "2") (pinfunction "2_2") (pintype "passive"))
    )
    (net (code "45") (name "Net-(Q16-PadE)") (class "Default")
      (node (ref "Q16") (pin "E") (pinfunction "E_E") (pintype "passive"))
      (node (ref "R49") (pin "1") (pinfunction "1_1") (pintype "passive"))
    )
    (net (code "46") (name "Net-(Q17-PadC)") (class "Default")
      (node (ref "Q17") (pin "C") (pinfunction "C_C") (pintype "passive"))
      (node (ref "R39") (pin "1") (pinfunction "1_1") (pintype "passive"))
      (node (ref "R40") (pin "1") (pinfunction "1_1") (pintype "passive"))
    )
    (net (code "47") (name "Net-(Q17-PadE)") (class "Default")
      (node (ref "Q17") (pin "E") (pinfunction "E_E") (pintype "passive"))
      (node (ref "R44") (pin "2") (pinfunction "2_2") (pintype "passive"))
    )
    (net (code "48") (name "Net-(Q18-PadC)") (class "Default")
      (node (ref "Q18") (pin "C") (pinfunction "C_C") (pintype "passive"))
      (node (ref "R41") (pin "2") (pinfunction "2_2") (pintype "passive"))
      (node (ref "R42") (pin "2") (pinfunction "2_2") (pintype "passive"))
    )
    (net (code "49") (name "Net-(Q18-PadE)") (class "Default")
      (node (ref "Q18") (pin "E") (pinfunction "E_E") (pintype "passive"))
      (node (ref "R43") (pin "1") (pinfunction "1_1") (pintype "passive"))
    )
    (net (code "50") (name "Net-(R3-Pad1)") (class "Default")
      (node (ref "R3") (pin "1") (pinfunction "1_1") (pintype "passive"))
      (node (ref "R4") (pin "2") (pinfunction "2_2") (pintype "passive"))
    )
    (net (code "51") (name "Net-(R19-Pad1)") (class "Default")
      (node (ref "R19") (pin "1") (pinfunction "1_1") (pintype "passive"))
      (node (ref "R20") (pin "2") (pinfunction "2_2") (pintype "passive"))
    )
    (net (code "52") (name "Net-(U$1A-D)") (class "Default")
      (node (ref "U$1") (pin "2") (pinfunction "D_2") (pintype "passive"))
      (node (ref "U$5") (pin "4") (pinfunction "C_4") (pintype "passive"))
      (node (ref "U$6") (pin "5") (pinfunction "E_5") (pintype "passive"))
    )
    (net (code "53") (name "Net-(U$1A-S)") (class "Default")
      (node (ref "R39") (pin "2") (pinfunction "2_2") (pintype "passive"))
      (node (ref "U$1") (pin "3") (pinfunction "S_3") (pintype "passive"))
    )
    (net (code "54") (name "Net-(U$1B-D)") (class "Default")
      (node (ref "U$1") (pin "5") (pinfunction "D_5") (pintype "passive"))
      (node (ref "U$5") (pin "6") (pinfunction "C_6") (pintype "passive"))
      (node (ref "U$6") (pin "2") (pinfunction "E_2") (pintype "passive"))
    )
    (net (code "55") (name "Net-(U$1B-S)") (class "Default")
      (node (ref "R40") (pin "2") (pinfunction "2_2") (pintype "passive"))
      (node (ref "U$1") (pin "6") (pinfunction "S_6") (pintype "passive"))
    )
    (net (code "56") (name "Net-(U$2A-B)") (class "Default")
      (node (ref "R29") (pin "2") (pinfunction "2_2") (pintype "passive"))
      (node (ref "R32") (pin "1") (pinfunction "1_1") (pintype "passive"))
      (node (ref "U$2") (pin "1") (pinfunction "B_1") (pintype "passive"))
      (node (ref "U$2") (pin "3") (pinfunction "B_3") (pintype "passive"))
    )
    (net (code "57") (name "Net-(U$2A-E)") (class "Default")
      (node (ref "U$2") (pin "5") (pinfunction "E_5") (pintype "passive"))
      (node (ref "U$3") (pin "6") (pinfunction "C_6") (pintype "passive"))
      (node (ref "U$4") (pin "2") (pinfunction "D_2") (pintype "passive"))
    )
    (net (code "58") (name "Net-(U$2B-E)") (class "Default")
      (node (ref "U$2") (pin "2") (pinfunction "E_2") (pintype "passive"))
      (node (ref "U$3") (pin "4") (pinfunction "C_4") (pintype "passive"))
      (node (ref "U$4") (pin "5") (pinfunction "D_5") (pintype "passive"))
    )
    (net (code "59") (name "Net-(U$3A-B)") (class "Default")
      (node (ref "LED1") (pin "A") (pinfunction "A_A") (pintype "passive"))
      (node (ref "R29") (pin "1") (pinfunction "1_1") (pintype "passive"))
      (node (ref "U$3") (pin "1") (pinfunction "B_1") (pintype "passive"))
      (node (ref "U$3") (pin "3") (pinfunction "B_3") (pintype "passive"))
    )
    (net (code "60") (name "Net-(U$3A-E)") (class "Default")
      (node (ref "R22") (pin "2") (pinfunction "2_2") (pintype "passive"))
      (node (ref "U$3") (pin "5") (pinfunction "E_5") (pintype "passive"))
    )
    (net (code "61") (name "Net-(U$3B-E)") (class "Default")
      (node (ref "R23") (pin "2") (pinfunction "2_2") (pintype "passive"))
      (node (ref "U$3") (pin "2") (pinfunction "E_2") (pintype "passive"))
    )
    (net (code "62") (name "Net-(U$4A-S)") (class "Default")
      (node (ref "R41") (pin "1") (pinfunction "1_1") (pintype "passive"))
      (node (ref "U$4") (pin "3") (pinfunction "S_3") (pintype "passive"))
    )
    (net (code "63") (name "Net-(U$4B-S)") (class "Default")
      (node (ref "R42") (pin "1") (pinfunction "1_1") (pintype "passive"))
      (node (ref "U$4") (pin "6") (pinfunction "S_6") (pintype "passive"))
    )
    (net (code "64") (name "Net-(U$5A-B)") (class "Default")
      (node (ref "LED2") (pin "C") (pinfunction "C_C") (pintype "passive"))
      (node (ref "R34") (pin "2") (pinfunction "2_2") (pintype "passive"))
      (node (ref "U$5") (pin "1") (pinfunction "B_1") (pintype "passive"))
      (node (ref "U$5") (pin "3") (pinfunction "B_3") (pintype "passive"))
    )
    (net (code "65") (name "Net-(U$5A-E)") (class "Default")
      (node (ref "R36") (pin "1") (pinfunction "1_1") (pintype "passive"))
      (node (ref "U$5") (pin "5") (pinfunction "E_5") (pintype "passive"))
    )
    (net (code "66") (name "Net-(U$5B-E)") (class "Default")
      (node (ref "R35") (pin "1") (pinfunction "1_1") (pintype "passive"))
      (node (ref "U$5") (pin "2") (pinfunction "E_2") (pintype "passive"))
    )
    (net (code "67") (name "Net-(U$6A-B)") (class "Default")
      (node (ref "R33") (pin "2") (pinfunction "2_2") (pintype "passive"))
      (node (ref "R34") (pin "1") (pinfunction "1_1") (pintype "passive"))
      (node (ref "U$6") (pin "1") (pinfunction "B_1") (pintype "passive"))
      (node (ref "U$6") (pin "3") (pinfunction "B_3") (pintype "passive"))
    )
    (net (code "68") (name "V+") (class "Default")
      (node (ref "C2") (pin "2") (pinfunction "2_2") (pintype "passive"))
      (node (ref "C5") (pin "2") (pinfunction "2_2") (pintype "passive"))
      (node (ref "C7") (pin "+") (pinfunction "+_+") (pintype "passive"))
      (node (ref "C8") (pin "+") (pinfunction "+_+") (pintype "passive"))
      (node (ref "IC1") (pin "7") (pinfunction "V+_7") (pintype "power_in"))
      (node (ref "IC2") (pin "7") (pinfunction "V+_7") (pintype "power_in"))
      (node (ref "LED2") (pin "A") (pinfunction "A_A") (pintype "passive"))
      (node (ref "LED3") (pin "A") (pinfunction "A_A") (pintype "passive"))
      (node (ref "LED5") (pin "A") (pinfunction "A_A") (pintype "passive"))
      (node (ref "LED7") (pin "A") (pinfunction "A_A") (pintype "passive"))
      (node (ref "Q1") (pin "C") (pinfunction "C_C") (pintype "passive"))
      (node (ref "Q13") (pin "C") (pinfunction "C_C") (pintype "passive"))
      (node (ref "Q14") (pin "C") (pinfunction "C_C") (pintype "passive"))
      (node (ref "Q5") (pin "C") (pinfunction "C_C") (pintype "passive"))
      (node (ref "Q8") (pin "C") (pinfunction "C_C") (pintype "passive"))
      (node (ref "Q9") (pin "C") (pinfunction "C_C") (pintype "passive"))
      (node (ref "R1") (pin "2") (pinfunction "2_2") (pintype "passive"))
      (node (ref "R15") (pin "2") (pinfunction "2_2") (pintype "passive"))
      (node (ref "R35") (pin "2") (pinfunction "2_2") (pintype "passive"))
      (node (ref "R36") (pin "2") (pinfunction "2_2") (pintype "passive"))
      (node (ref "R43") (pin "2") (pinfunction "2_2") (pintype "passive"))
      (node (ref "X1") (pin "2") (pinfunction "KL_2") (pintype "passive"))
      (node (ref "X2") (pin "1") (pinfunction "KL_1") (pintype "passive"))
    )
    (net (code "69") (name "V-") (class "Default")
      (node (ref "C10") (pin "-") (pinfunction "-_-") (pintype "passive"))
      (node (ref "C3") (pin "1") (pinfunction "1_1") (pintype "passive"))
      (node (ref "C6") (pin "1") (pinfunction "1_1") (pintype "passive"))
      (node (ref "C9") (pin "-") (pinfunction "-_-") (pintype "passive"))
      (node (ref "IC1") (pin "4") (pinfunction "V-_4") (pintype "power_in"))
      (node (ref "IC2") (pin "4") (pinfunction "V-_4") (pintype "power_in"))
      (node (ref "LED1") (pin "C") (pinfunction "C_C") (pintype "passive"))
      (node (ref "LED4") (pin "C") (pinfunction "C_C") (pintype "passive"))
      (node (ref "LED6") (pin "C") (pinfunction "C_C") (pintype "passive"))
      (node (ref "LED8") (pin "C") (pinfunction "C_C") (pintype "passive"))
      (node (ref "Q10") (pin "C") (pinfunction "C_C") (pintype "passive"))
      (node (ref "Q15") (pin "C") (pinfunction "C_C") (pintype "passive"))
      (node (ref "Q16") (pin "C") (pinfunction "C_C") (pintype "passive"))
      (node (ref "Q2") (pin "C") (pinfunction "C_C") (pintype "passive"))
      (node (ref "Q6") (pin "C") (pinfunction "C_C") (pintype "passive"))
      (node (ref "Q7") (pin "C") (pinfunction "C_C") (pintype "passive"))
      (node (ref "R18") (pin "1") (pinfunction "1_1") (pintype "passive"))
      (node (ref "R2") (pin "1") (pinfunction "1_1") (pintype "passive"))
      (node (ref "R22") (pin "1") (pinfunction "1_1") (pintype "passive"))
      (node (ref "R23") (pin "1") (pinfunction "1_1") (pintype "passive"))
      (node (ref "R44") (pin "1") (pinfunction "1_1") (pintype "passive"))
      (node (ref "X1") (pin "1") (pinfunction "KL_1") (pintype "passive"))
      (node (ref "X2") (pin "2") (pinfunction "KL_2") (pintype "passive"))
    )
    (net (code "70") (name "unconnected-(IC1-TRIM1-Pad1)") (class "Default")
      (node (ref "IC1") (pin "1") (pinfunction "TRIM1_1") (pintype "passive"))
    )
    (net (code "71") (name "unconnected-(IC1-TRIM2-Pad5)") (class "Default")
      (node (ref "IC1") (pin "5") (pinfunction "TRIM2_5") (pintype "passive"))
    )
    (net (code "72") (name "unconnected-(IC2-TRIM1-Pad1)") (class "Default")
      (node (ref "IC2") (pin "1") (pinfunction "TRIM1_1") (pintype "passive"))
    )
    (net (code "73") (name "unconnected-(IC2-TRIM2-Pad5)") (class "Default")
      (node (ref "IC2") (pin "5") (pinfunction "TRIM2_5") (pintype "passive"))
    )
  )
)
